# SC2_Schem.net
KiCad netlist of a schematic drawn in EAGLE
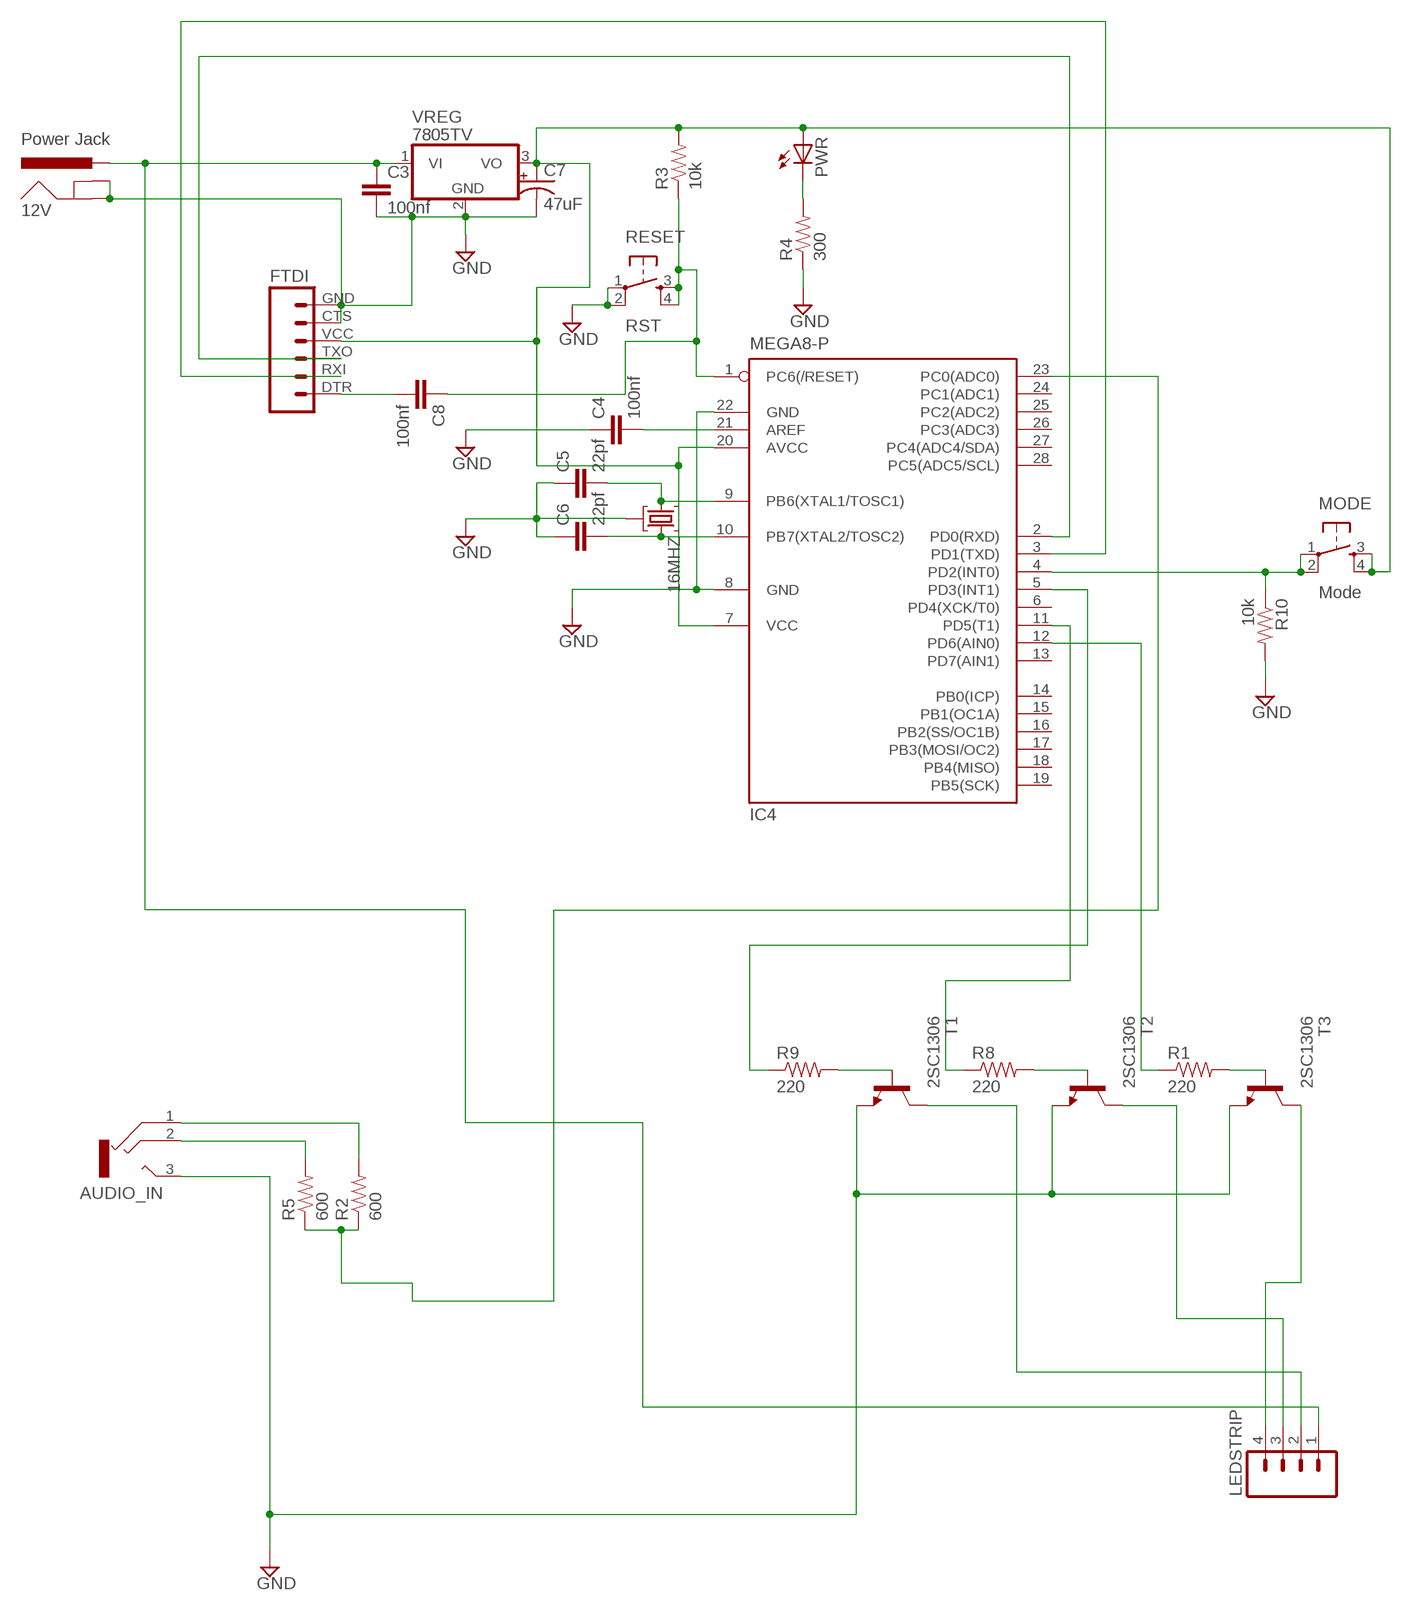
[diagram p0: schematic, sheet 1]

(export (version "E")
  (design (tool "Eeschema 10.0.6"))
  (components
    (comp (ref "12V")
      (value "Power Jack")
      (footprint "eagle-import:POWER_JACK_PTH")
      (libsource (lib "eagle-import") (part "POWER_JACKPTH"))
    )
    (comp (ref "16MHZ")
      (value "10G7A-12.5KHZ")
      (footprint "eagle-import:HC49U")
      (libsource (lib "eagle-import") (part "10G7A-12.5KHZ"))
    )
    (comp (ref "AUDIO_IN")
      (value "1503_04")
      (footprint "eagle-import:1503_04")
      (libsource (lib "eagle-import") (part "1503_04"))
    )
    (comp (ref "C3")
      (value "100nf")
      (footprint "eagle-import:CAP-PTH-5MM")
      (libsource (lib "eagle-import") (part "CAPPTH1"))
    )
    (comp (ref "C4")
      (value "100nf")
      (footprint "eagle-import:CAP-PTH-5MM")
      (libsource (lib "eagle-import") (part "CAPPTH1"))
    )
    (comp (ref "C5")
      (value "22pf")
      (footprint "eagle-import:CAP-PTH-5MM")
      (libsource (lib "eagle-import") (part "CAPPTH1"))
    )
    (comp (ref "C6")
      (value "22pf")
      (footprint "eagle-import:CAP-PTH-5MM")
      (libsource (lib "eagle-import") (part "CAPPTH1"))
    )
    (comp (ref "C7")
      (value "47uF")
      (footprint "eagle-import:CPOL-RADIAL-100UF-25V")
      (libsource (lib "eagle-import") (part "CAP_POLPTH1"))
    )
    (comp (ref "C8")
      (value "100nf")
      (footprint "eagle-import:CAP-PTH-5MM")
      (libsource (lib "eagle-import") (part "CAPPTH1"))
    )
    (comp (ref "FTDI")
      (value "FTDI_BASICPTH")
      (footprint "eagle-import:FTDI_BASIC")
      (libsource (lib "eagle-import") (part "FTDI_BASICPTH"))
    )
    (comp (ref "IC4")
      (value "MEGA8-P")
      (footprint "eagle-import:DIL28-3")
      (libsource (lib "eagle-import") (part "MEGA8-P"))
    )
    (comp (ref "LEDSTRIP")
      (value "M041X04_NO_SILK")
      (footprint "eagle-import:1X04_NO_SILK")
      (libsource (lib "eagle-import") (part "M041X04_NO_SILK"))
    )
    (comp (ref "MODE")
      (value "Mode")
      (footprint "eagle-import:TACTILE-PTH")
      (libsource (lib "eagle-import") (part "TAC_SWITCHPTH"))
    )
    (comp (ref "PWR")
      (value "LED5MM")
      (footprint "eagle-import:LED5MM")
      (libsource (lib "eagle-import") (part "LED5MM"))
    )
    (comp (ref "R1")
      (value "220")
      (footprint "eagle-import:AXIAL-0.3")
      (libsource (lib "eagle-import") (part "RESISTORAXIAL-0.3"))
    )
    (comp (ref "R2")
      (value "600")
      (footprint "eagle-import:AXIAL-0.3")
      (libsource (lib "eagle-import") (part "RESISTORAXIAL-0.3"))
    )
    (comp (ref "R3")
      (value "10k")
      (footprint "eagle-import:AXIAL-0.3EZ")
      (libsource (lib "eagle-import") (part "RESISTOREZ"))
    )
    (comp (ref "R4")
      (value "300")
      (footprint "eagle-import:AXIAL-0.3EZ")
      (libsource (lib "eagle-import") (part "RESISTOREZ"))
    )
    (comp (ref "R5")
      (value "600")
      (footprint "eagle-import:AXIAL-0.3")
      (libsource (lib "eagle-import") (part "RESISTORAXIAL-0.3"))
    )
    (comp (ref "R8")
      (value "220")
      (footprint "eagle-import:AXIAL-0.3")
      (libsource (lib "eagle-import") (part "RESISTORAXIAL-0.3"))
    )
    (comp (ref "R9")
      (value "220")
      (footprint "eagle-import:AXIAL-0.3")
      (libsource (lib "eagle-import") (part "RESISTORAXIAL-0.3"))
    )
    (comp (ref "R10")
      (value "10k")
      (footprint "eagle-import:AXIAL-0.3")
      (libsource (lib "eagle-import") (part "RESISTORAXIAL-0.3"))
    )
    (comp (ref "RESET")
      (value "RST")
      (footprint "eagle-import:TACTILE-PTH")
      (libsource (lib "eagle-import") (part "TAC_SWITCHPTH"))
    )
    (comp (ref "T1")
      (value "2SC1306")
      (footprint "eagle-import:TO220BV")
      (libsource (lib "eagle-import") (part "2SC1306"))
    )
    (comp (ref "T2")
      (value "2SC1306")
      (footprint "eagle-import:TO220BV")
      (libsource (lib "eagle-import") (part "2SC1306"))
    )
    (comp (ref "T3")
      (value "2SC1306")
      (footprint "eagle-import:TO220BV")
      (libsource (lib "eagle-import") (part "2SC1306"))
    )
    (comp (ref "VREG")
      (value "7805TV")
      (footprint "eagle-import:TO220V")
      (libsource (lib "eagle-import") (part "78TV05"))
    )
  )
  (nets
    (net (code "1") (name "GND") (class "Default")
      (node (ref "12V") (pin "GND") (pinfunction "GND_GND") (pintype "bidirectional"))
      (node (ref "12V") (pin "GNDBREAK") (pinfunction "GNDBREAK_GNDBREAK") (pintype "bidirectional"))
      (node (ref "16MHZ") (pin "2") (pinfunction "2_2") (pintype "passive"))
      (node (ref "AUDIO_IN") (pin "3") (pinfunction "2_3") (pintype "passive"))
      (node (ref "C3") (pin "2") (pinfunction "2_2") (pintype "passive"))
      (node (ref "C4") (pin "1") (pinfunction "1_1") (pintype "passive"))
      (node (ref "C5") (pin "1") (pinfunction "1_1") (pintype "passive"))
      (node (ref "C6") (pin "1") (pinfunction "1_1") (pintype "passive"))
      (node (ref "C7") (pin "2") (pinfunction "-_2") (pintype "passive"))
      (node (ref "FTDI") (pin "CTS") (pinfunction "5_CTS") (pintype "passive"))
      (node (ref "FTDI") (pin "GND") (pinfunction "6_GND") (pintype "passive"))
      (node (ref "IC4") (pin "22") (pinfunction "GND_22") (pintype "power_in"))
      (node (ref "IC4") (pin "8") (pinfunction "GND_8") (pintype "power_in"))
      (node (ref "R10") (pin "P$2") (pinfunction "2_P$2") (pintype "passive"))
      (node (ref "R4") (pin "P$1") (pinfunction "1_P$1") (pintype "passive"))
      (node (ref "RESET") (pin "1") (pinfunction "1_1") (pintype "passive"))
      (node (ref "RESET") (pin "2") (pinfunction "2_2") (pintype "passive"))
      (node (ref "T1") (pin "3") (pinfunction "E_3") (pintype "passive"))
      (node (ref "T2") (pin "3") (pinfunction "E_3") (pintype "passive"))
      (node (ref "T3") (pin "3") (pinfunction "E_3") (pintype "passive"))
      (node (ref "VREG") (pin "2") (pinfunction "GND_2") (pintype "passive"))
    )
    (net (code "2") (name "Net-(AUDIO_IN-3)") (class "Default")
      (node (ref "AUDIO_IN") (pin "2") (pinfunction "3_2") (pintype "passive"))
      (node (ref "R5") (pin "P$2") (pinfunction "2_P$2") (pintype "passive"))
    )
    (net (code "3") (name "Net-(C7-+)") (class "Default")
      (node (ref "C7") (pin "1") (pinfunction "+_1") (pintype "passive"))
      (node (ref "FTDI") (pin "VCC") (pinfunction "4_VCC") (pintype "passive"))
      (node (ref "IC4") (pin "20") (pinfunction "AVCC_20") (pintype "power_in"))
      (node (ref "IC4") (pin "7") (pinfunction "VCC_7") (pintype "power_in"))
      (node (ref "MODE") (pin "3") (pinfunction "3_3") (pintype "passive"))
      (node (ref "MODE") (pin "4") (pinfunction "4_4") (pintype "passive"))
      (node (ref "PWR") (pin "A") (pinfunction "A_A") (pintype "passive"))
      (node (ref "R3") (pin "P$2") (pinfunction "2_P$2") (pintype "passive"))
      (node (ref "VREG") (pin "3") (pinfunction "VO_3") (pintype "passive"))
    )
    (net (code "4") (name "Net-(FTDI-1)") (class "Default")
      (node (ref "C8") (pin "2") (pinfunction "2_2") (pintype "passive"))
      (node (ref "FTDI") (pin "DTR") (pinfunction "1_DTR") (pintype "passive"))
    )
    (net (code "5") (name "Net-(FTDI-2)") (class "Default")
      (node (ref "FTDI") (pin "RXI") (pinfunction "2_RXI") (pintype "passive"))
      (node (ref "IC4") (pin "3") (pinfunction "PD1(TXD)_3") (pintype "bidirectional"))
    )
    (net (code "6") (name "Net-(FTDI-3)") (class "Default")
      (node (ref "FTDI") (pin "TXO") (pinfunction "3_TXO") (pintype "passive"))
      (node (ref "IC4") (pin "2") (pinfunction "PD0(RXD)_2") (pintype "bidirectional"))
    )
    (net (code "7") (name "Net-(IC4-AREF)") (class "Default")
      (node (ref "C4") (pin "2") (pinfunction "2_2") (pintype "passive"))
      (node (ref "IC4") (pin "21") (pinfunction "AREF_21") (pintype "passive"))
    )
    (net (code "8") (name "Net-(IC4-PB6(XTAL1{slash}TOSC1))") (class "Default")
      (node (ref "16MHZ") (pin "1") (pinfunction "1_1") (pintype "passive"))
      (node (ref "C5") (pin "2") (pinfunction "2_2") (pintype "passive"))
      (node (ref "IC4") (pin "9") (pinfunction "PB6(XTAL1/TOSC1)_9") (pintype "bidirectional"))
    )
    (net (code "9") (name "Net-(IC4-PB7(XTAL2{slash}TOSC2))") (class "Default")
      (node (ref "16MHZ") (pin "3") (pinfunction "3_3") (pintype "passive"))
      (node (ref "C6") (pin "2") (pinfunction "2_2") (pintype "passive"))
      (node (ref "IC4") (pin "10") (pinfunction "PB7(XTAL2/TOSC2)_10") (pintype "bidirectional"))
    )
    (net (code "10") (name "Net-(IC4-PC0(ADC0))") (class "Default")
      (node (ref "IC4") (pin "23") (pinfunction "PC0(ADC0)_23") (pintype "bidirectional"))
      (node (ref "R2") (pin "P$1") (pinfunction "1_P$1") (pintype "passive"))
      (node (ref "R5") (pin "P$1") (pinfunction "1_P$1") (pintype "passive"))
    )
    (net (code "11") (name "Net-(IC4-PC6({slash}RESET))") (class "Default")
      (node (ref "C8") (pin "1") (pinfunction "1_1") (pintype "passive"))
      (node (ref "IC4") (pin "1") (pinfunction "PC6(/RESET)_1") (pintype "bidirectional"))
      (node (ref "R3") (pin "P$1") (pinfunction "1_P$1") (pintype "passive"))
      (node (ref "RESET") (pin "3") (pinfunction "3_3") (pintype "passive"))
      (node (ref "RESET") (pin "4") (pinfunction "4_4") (pintype "passive"))
    )
    (net (code "12") (name "Net-(IC4-PD2(INT0))") (class "Default")
      (node (ref "IC4") (pin "4") (pinfunction "PD2(INT0)_4") (pintype "bidirectional"))
      (node (ref "MODE") (pin "1") (pinfunction "1_1") (pintype "passive"))
      (node (ref "MODE") (pin "2") (pinfunction "2_2") (pintype "passive"))
      (node (ref "R10") (pin "P$1") (pinfunction "1_P$1") (pintype "passive"))
    )
    (net (code "13") (name "Net-(IC4-PD3(INT1))") (class "Default")
      (node (ref "IC4") (pin "5") (pinfunction "PD3(INT1)_5") (pintype "bidirectional"))
      (node (ref "R9") (pin "P$1") (pinfunction "1_P$1") (pintype "passive"))
    )
    (net (code "14") (name "Net-(IC4-PD5(T1))") (class "Default")
      (node (ref "IC4") (pin "11") (pinfunction "PD5(T1)_11") (pintype "bidirectional"))
      (node (ref "R8") (pin "P$1") (pinfunction "1_P$1") (pintype "passive"))
    )
    (net (code "15") (name "Net-(IC4-PD6(AIN0))") (class "Default")
      (node (ref "IC4") (pin "12") (pinfunction "PD6(AIN0)_12") (pintype "bidirectional"))
      (node (ref "R1") (pin "P$1") (pinfunction "1_P$1") (pintype "passive"))
    )
    (net (code "16") (name "Net-(PWR-C)") (class "Default")
      (node (ref "PWR") (pin "K") (pinfunction "C_K") (pintype "passive"))
      (node (ref "R4") (pin "P$2") (pinfunction "2_P$2") (pintype "passive"))
    )
    (net (code "17") (name "Net-(R1-2)") (class "Default")
      (node (ref "R1") (pin "P$2") (pinfunction "2_P$2") (pintype "passive"))
      (node (ref "T3") (pin "1") (pinfunction "B_1") (pintype "passive"))
    )
    (net (code "18") (name "Net-(R2-2)") (class "Default")
      (node (ref "AUDIO_IN") (pin "1") (pinfunction "1_1") (pintype "passive"))
      (node (ref "R2") (pin "P$2") (pinfunction "2_P$2") (pintype "passive"))
    )
    (net (code "19") (name "Net-(R8-2)") (class "Default")
      (node (ref "R8") (pin "P$2") (pinfunction "2_P$2") (pintype "passive"))
      (node (ref "T2") (pin "1") (pinfunction "B_1") (pintype "passive"))
    )
    (net (code "20") (name "Net-(R9-2)") (class "Default")
      (node (ref "R9") (pin "P$2") (pinfunction "2_P$2") (pintype "passive"))
      (node (ref "T1") (pin "1") (pinfunction "B_1") (pintype "passive"))
    )
    (net (code "21") (name "Net-(T1-C)") (class "Default")
      (node (ref "LEDSTRIP") (pin "2") (pinfunction "2_2") (pintype "passive"))
      (node (ref "T1") (pin "2") (pinfunction "C_2") (pintype "passive"))
    )
    (net (code "22") (name "Net-(T2-C)") (class "Default")
      (node (ref "LEDSTRIP") (pin "3") (pinfunction "3_3") (pintype "passive"))
      (node (ref "T2") (pin "2") (pinfunction "C_2") (pintype "passive"))
    )
    (net (code "23") (name "Net-(T3-C)") (class "Default")
      (node (ref "LEDSTRIP") (pin "4") (pinfunction "4_4") (pintype "passive"))
      (node (ref "T3") (pin "2") (pinfunction "C_2") (pintype "passive"))
    )
    (net (code "24") (name "Net-(VREG-VI)") (class "Default")
      (node (ref "12V") (pin "PWR") (pinfunction "PWR_PWR") (pintype "bidirectional"))
      (node (ref "C3") (pin "1") (pinfunction "1_1") (pintype "passive"))
      (node (ref "LEDSTRIP") (pin "1") (pinfunction "1_1") (pintype "passive"))
      (node (ref "VREG") (pin "1") (pinfunction "VI_1") (pintype "input"))
    )
    (net (code "25") (name "unconnected-(IC4-PB0(ICP)-Pad14)") (class "Default")
      (node (ref "IC4") (pin "14") (pinfunction "PB0(ICP)_14") (pintype "bidirectional"))
    )
    (net (code "26") (name "unconnected-(IC4-PB1(OC1A)-Pad15)") (class "Default")
      (node (ref "IC4") (pin "15") (pinfunction "PB1(OC1A)_15") (pintype "bidirectional"))
    )
    (net (code "27") (name "unconnected-(IC4-PB2(SS{slash}OC1B)-Pad16)") (class "Default")
      (node (ref "IC4") (pin "16") (pinfunction "PB2(SS/OC1B)_16") (pintype "bidirectional"))
    )
    (net (code "28") (name "unconnected-(IC4-PB3(MOSI{slash}OC2)-Pad17)") (class "Default")
      (node (ref "IC4") (pin "17") (pinfunction "PB3(MOSI/OC2)_17") (pintype "bidirectional"))
    )
    (net (code "29") (name "unconnected-(IC4-PB4(MISO)-Pad18)") (class "Default")
      (node (ref "IC4") (pin "18") (pinfunction "PB4(MISO)_18") (pintype "bidirectional"))
    )
    (net (code "30") (name "unconnected-(IC4-PB5(SCK)-Pad19)") (class "Default")
      (node (ref "IC4") (pin "19") (pinfunction "PB5(SCK)_19") (pintype "bidirectional"))
    )
    (net (code "31") (name "unconnected-(IC4-PC1(ADC1)-Pad24)") (class "Default")
      (node (ref "IC4") (pin "24") (pinfunction "PC1(ADC1)_24") (pintype "bidirectional"))
    )
    (net (code "32") (name "unconnected-(IC4-PC2(ADC2)-Pad25)") (class "Default")
      (node (ref "IC4") (pin "25") (pinfunction "PC2(ADC2)_25") (pintype "bidirectional"))
    )
    (net (code "33") (name "unconnected-(IC4-PC3(ADC3)-Pad26)") (class "Default")
      (node (ref "IC4") (pin "26") (pinfunction "PC3(ADC3)_26") (pintype "bidirectional"))
    )
    (net (code "34") (name "unconnected-(IC4-PC4(ADC4{slash}SDA)-Pad27)") (class "Default")
      (node (ref "IC4") (pin "27") (pinfunction "PC4(ADC4/SDA)_27") (pintype "bidirectional"))
    )
    (net (code "35") (name "unconnected-(IC4-PC5(ADC5{slash}SCL)-Pad28)") (class "Default")
      (node (ref "IC4") (pin "28") (pinfunction "PC5(ADC5/SCL)_28") (pintype "bidirectional"))
    )
    (net (code "36") (name "unconnected-(IC4-PD4(XCK{slash}T0)-Pad6)") (class "Default")
      (node (ref "IC4") (pin "6") (pinfunction "PD4(XCK/T0)_6") (pintype "bidirectional"))
    )
    (net (code "37") (name "unconnected-(IC4-PD7(AIN1)-Pad13)") (class "Default")
      (node (ref "IC4") (pin "13") (pinfunction "PD7(AIN1)_13") (pintype "bidirectional"))
    )
  )
)
